# Schematic.net
KiCad netlist of a schematic drawn in EasyEDA
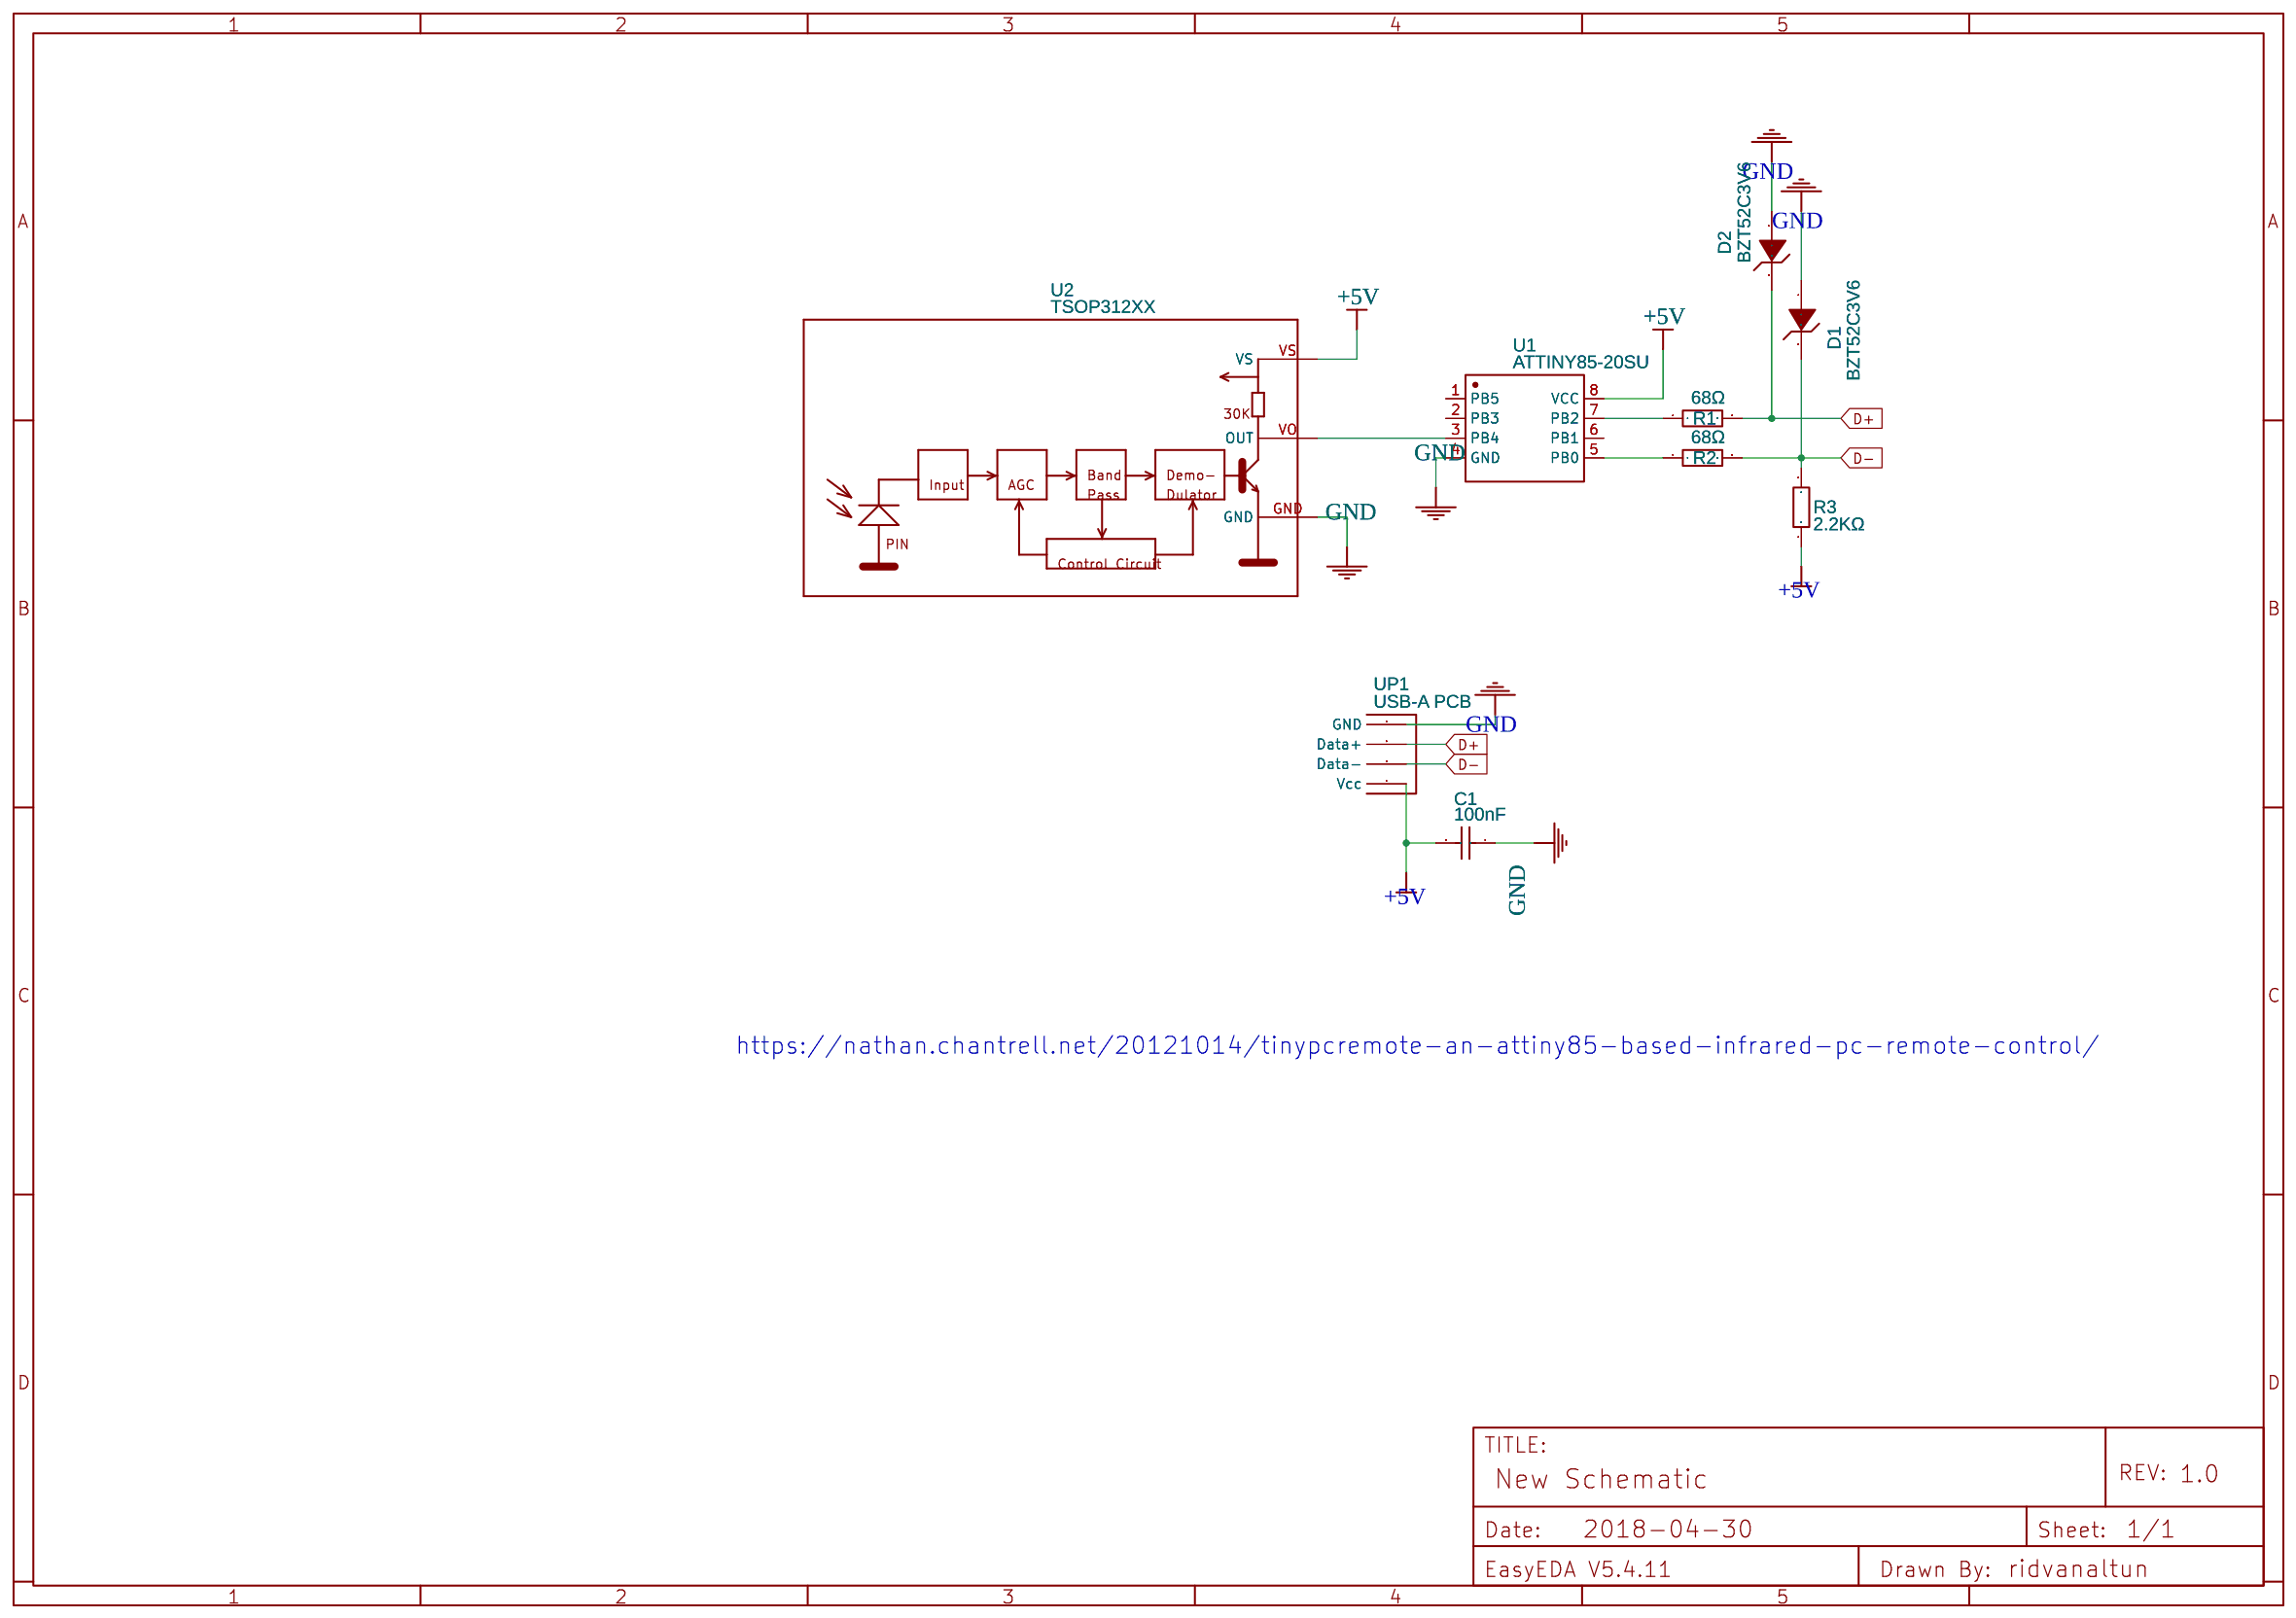
[diagram p0: schematic sheet]

(export (version "E")
  (design (tool "Eeschema 10.0.6"))
  (components
    (comp (ref "C1")
      (value "100nF")
      (fields (field (name "BOM_Manufacturer Part") "0603B104K500NT"))
      (libsource (lib "") (part "0603B104K500NT"))
    )
    (comp (ref "D1") (value "BZT52C3V6") (libsource (lib "") (part "Unknown_905_155")))
    (comp (ref "D2") (value "BZT52C3V6") (libsource (lib "") (part "Unknown_890_120")))
    (comp (ref "R1")
      (value "68Ω")
      (fields (field (name "BOM_Manufacturer Part") "RTT0368R0FTP"))
      (libsource (lib "") (part "RTT0368R0FTP"))
    )
    (comp (ref "R2")
      (value "68Ω")
      (fields (field (name "BOM_Manufacturer Part") "RTT0368R0FTP"))
      (libsource (lib "") (part "RTT0368R0FTP"))
    )
    (comp (ref "R3")
      (value "2.2KΩ")
      (fields (field (name "BOM_Manufacturer Part") "CR0603FA2201G"))
      (libsource (lib "") (part "CR0603FA2201G"))
    )
    (comp (ref "U1") (value "ATTINY85-20SU") (libsource (lib "") (part "Unknown_765_185")))
    (comp (ref "U2")
      (value "TSOP312XX")
      (fields (field (name "BOM_Manufacturer Part") "?"))
      (libsource (lib "") (part "Unknown_550_235"))
    )
    (comp (ref "UP1")
      (value "USB-A PCB")
      (fields (field (name "BOM_Manufacturer Part") "New SchematicLib"))
      (libsource (lib "") (part "Unknown_665_340"))
    )
  )
  (nets
    (net (code "1") (name "+5V") (class "Default")
      (node (ref "C1") (pin "2") (pinfunction "2_2") (pintype "input"))
      (node (ref "R3") (pin "1") (pinfunction "1_1") (pintype "input"))
      (node (ref "U1") (pin "8") (pinfunction "VCC_8") (pintype "unspecified"))
      (node (ref "U2") (pin "VS") (pinfunction "VS_VS") (pintype "passive"))
      (node (ref "UP1") (pin "4") (pinfunction "Vcc_4") (pintype "unspecified"))
    )
    (net (code "2") (name "D+") (class "Default")
      (node (ref "D2") (pin "2") (pinfunction "K_2") (pintype "unspecified"))
      (node (ref "R1") (pin "2") (pinfunction "2_2") (pintype "input"))
      (node (ref "UP1") (pin "2") (pinfunction "Data+_2") (pintype "unspecified"))
    )
    (net (code "3") (name "D-") (class "Default")
      (node (ref "D1") (pin "2") (pinfunction "K_2") (pintype "unspecified"))
      (node (ref "R2") (pin "2") (pinfunction "2_2") (pintype "input"))
      (node (ref "R3") (pin "2") (pinfunction "2_2") (pintype "input"))
      (node (ref "UP1") (pin "3") (pinfunction "Data-_3") (pintype "unspecified"))
    )
    (net (code "4") (name "GND") (class "Default")
      (node (ref "C1") (pin "1") (pinfunction "1_1") (pintype "input"))
      (node (ref "D1") (pin "1") (pinfunction "A_1") (pintype "unspecified"))
      (node (ref "D2") (pin "1") (pinfunction "A_1") (pintype "unspecified"))
      (node (ref "U1") (pin "4") (pinfunction "GND_4") (pintype "unspecified"))
      (node (ref "U2") (pin "GND") (pinfunction "GND_GND") (pintype "unspecified"))
      (node (ref "UP1") (pin "1") (pinfunction "GND_1") (pintype "unspecified"))
    )
    (net (code "5") (name "Net-(U1-PB0)") (class "Default")
      (node (ref "R2") (pin "1") (pinfunction "1_1") (pintype "input"))
      (node (ref "U1") (pin "5") (pinfunction "PB0_5") (pintype "unspecified"))
    )
    (net (code "6") (name "Net-(U1-PB2)") (class "Default")
      (node (ref "R1") (pin "1") (pinfunction "1_1") (pintype "input"))
      (node (ref "U1") (pin "7") (pinfunction "PB2_7") (pintype "unspecified"))
    )
    (net (code "7") (name "Net-(U1-PB4)") (class "Default")
      (node (ref "U1") (pin "3") (pinfunction "PB4_3") (pintype "unspecified"))
      (node (ref "U2") (pin "VO") (pinfunction "OUT_VO") (pintype "output"))
    )
    (net (code "8") (name "unconnected-(U1-PB1-Pad6)") (class "Default")
      (node (ref "U1") (pin "6") (pinfunction "PB1_6") (pintype "unspecified"))
    )
    (net (code "9") (name "unconnected-(U1-PB3-Pad2)") (class "Default")
      (node (ref "U1") (pin "2") (pinfunction "PB3_2") (pintype "unspecified"))
    )
    (net (code "10") (name "unconnected-(U1-PB5-Pad1)") (class "Default")
      (node (ref "U1") (pin "1") (pinfunction "PB5_1") (pintype "unspecified"))
    )
  )
)
